# Carte_Herse_2020.net
KiCad netlist of a schematic drawn in Altium Designer
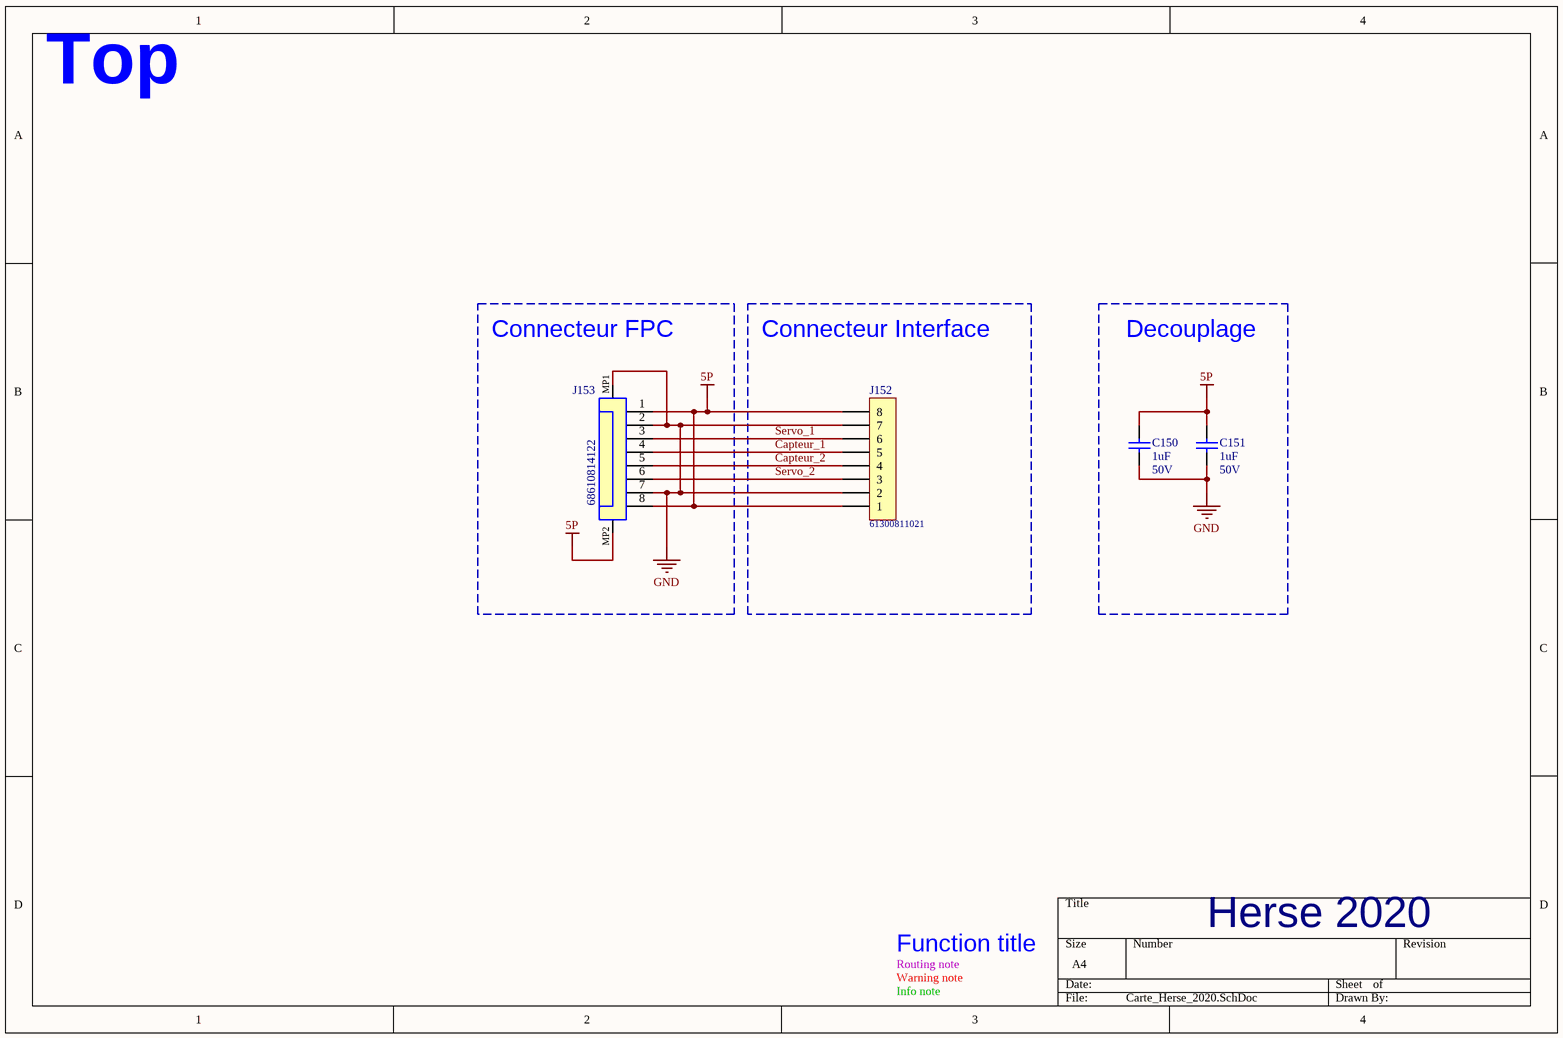
[diagram p0: Carte_Herse_2020.SchDoc]

(export (version "E")
  (design (tool "Eeschema 10.0.6"))
  (components
    (comp (ref "C150")
      (value "1uF")
      (footprint "WCAP-CSGP_0805, 2x1.25x1.25")
      (description "CAP CER 1uF 50V X7R 0805")
      (fields
        (field (name "MANUFACTURER") "Wurth Elektronik")
        (field (name "MANUFACTURER PART NUMBER") "885012207103")
        (field (name "RATEDVOLTAGE") "50V")
      )
      (libsource (lib "Condensateur") (part "WCAP-CSGP, 885012207103"))
    )
    (comp (ref "C151")
      (value "1uF")
      (footprint "WCAP-CSGP_0805, 2x1.25x1.25")
      (description "CAP CER 1uF 50V X7R 0805")
      (fields
        (field (name "MANUFACTURER") "Wurth Elektronik")
        (field (name "MANUFACTURER PART NUMBER") "885012207103")
        (field (name "RATEDVOLTAGE") "50V")
      )
      (libsource (lib "Condensateur") (part "WCAP-CSGP, 885012207103"))
    )
    (comp (ref "J152")
      (value "61300811021")
      (footprint "61300811021")
      (description "WR-PHD Header THT 2.54mm, Single Row, Angled, 8pin")
      (fields (field (name "MANUFACTURER") "Wurth Electronics Inc."))
      (libsource (lib "Connecteurs") (part "61300811021"))
    )
    (comp (ref "J153")
      (value "68610814122")
      (footprint "68610814122")
      (description "WR-FPC SMT ZIF Horizontal Top Contact, pitch 1mm, 8p")
      (fields (field (name "MANUFACTURER") "Wurth Electronics Inc."))
      (libsource (lib "Connecteurs") (part "68610814122"))
    )
  )
  (nets
    (net (code "1") (name "/Capteur_1") (class "Default")
      (node (ref "J152") (pin "5") (pinfunction "5_5") (pintype "passive"))
      (node (ref "J153") (pin "4") (pinfunction "4_4") (pintype "passive"))
    )
    (net (code "2") (name "/Capteur_2") (class "Default")
      (node (ref "J152") (pin "4") (pinfunction "4_4") (pintype "passive"))
      (node (ref "J153") (pin "5") (pinfunction "5_5") (pintype "passive"))
    )
    (net (code "3") (name "/Servo_1") (class "Default")
      (node (ref "J152") (pin "6") (pinfunction "6_6") (pintype "passive"))
      (node (ref "J153") (pin "3") (pinfunction "3_3") (pintype "passive"))
    )
    (net (code "4") (name "/Servo_2") (class "Default")
      (node (ref "J152") (pin "3") (pinfunction "3_3") (pintype "passive"))
      (node (ref "J153") (pin "6") (pinfunction "6_6") (pintype "passive"))
    )
    (net (code "5") (name "5P") (class "Default")
      (node (ref "C150") (pin "1") (pinfunction "1_1") (pintype "passive"))
      (node (ref "C151") (pin "1") (pinfunction "1_1") (pintype "passive"))
      (node (ref "J152") (pin "1") (pinfunction "1_1") (pintype "passive"))
      (node (ref "J152") (pin "8") (pinfunction "8_8") (pintype "passive"))
      (node (ref "J153") (pin "1") (pinfunction "1_1") (pintype "passive"))
      (node (ref "J153") (pin "8") (pinfunction "8_8") (pintype "passive"))
      (node (ref "J153") (pin "MP2") (pinfunction "MP2_MP2") (pintype "passive"))
    )
    (net (code "6") (name "GND") (class "Default")
      (node (ref "C150") (pin "2") (pinfunction "2_2") (pintype "passive"))
      (node (ref "C151") (pin "2") (pinfunction "2_2") (pintype "passive"))
      (node (ref "J152") (pin "2") (pinfunction "2_2") (pintype "passive"))
      (node (ref "J152") (pin "7") (pinfunction "7_7") (pintype "passive"))
      (node (ref "J153") (pin "2") (pinfunction "2_2") (pintype "passive"))
      (node (ref "J153") (pin "7") (pinfunction "7_7") (pintype "passive"))
      (node (ref "J153") (pin "MP1") (pinfunction "MP1_MP1") (pintype "passive"))
    )
  )
)
